# suntile.net
KiCad netlist of a schematic drawn in Altium Designer
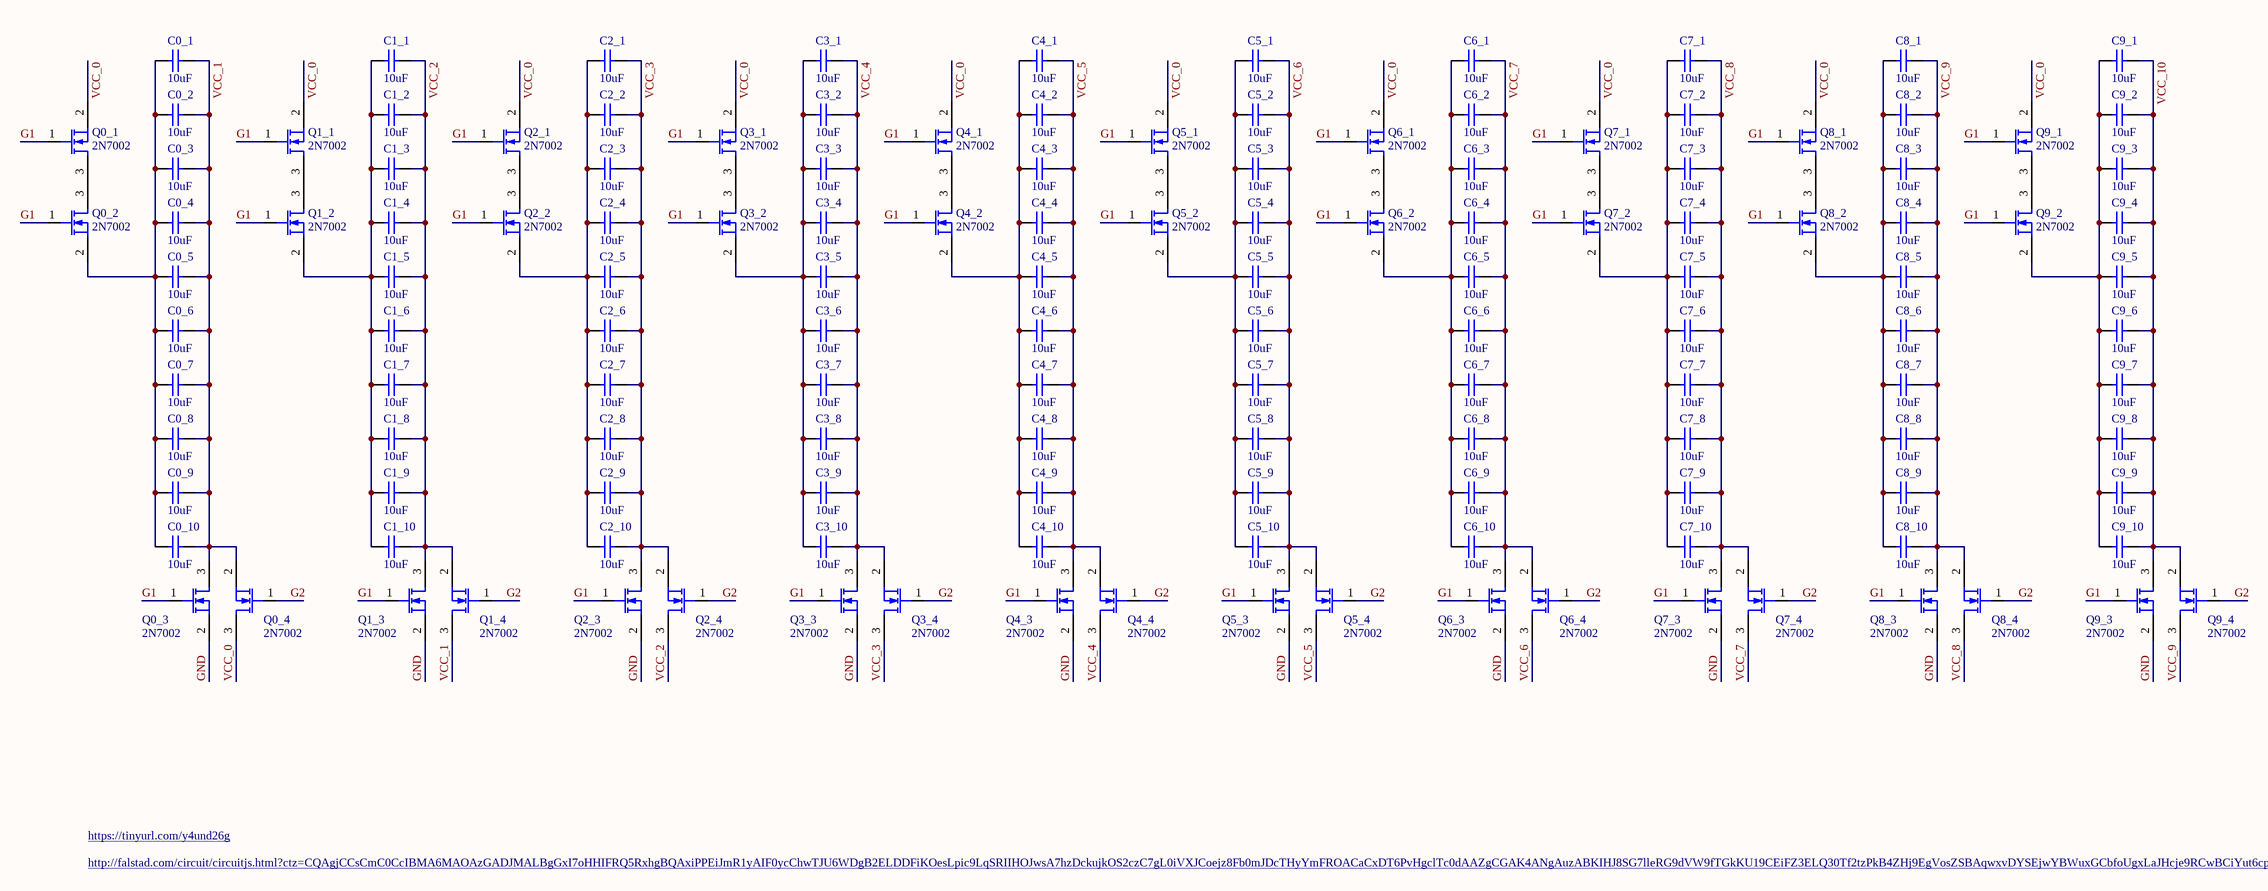
[diagram p0: suntile.SchDoc]

(export (version "E")
  (design (tool "Eeschema 10.0.6"))
  (components
    (comp (ref "C0_1")
      (value "10uF")
      (footprint "C_0402")
      (description "C - CAPACITOR - MLCC - 10uF - 6.3V - 0402")
      (fields (field (name "LCSC PART #") "C15525") (field (name "Comment") "CL05A106MQ5NUNC"))
      (libsource (lib "JLC_PCB") (part "CL05A106MQ5NUNC"))
    )
    (comp (ref "C0_2")
      (value "10uF")
      (footprint "C_0402")
      (description "C - CAPACITOR - MLCC - 10uF - 6.3V - 0402")
      (fields (field (name "LCSC PART #") "C15525") (field (name "Comment") "CL05A106MQ5NUNC"))
      (libsource (lib "JLC_PCB") (part "CL05A106MQ5NUNC"))
    )
    (comp (ref "C0_3")
      (value "10uF")
      (footprint "C_0402")
      (description "C - CAPACITOR - MLCC - 10uF - 6.3V - 0402")
      (fields (field (name "LCSC PART #") "C15525") (field (name "Comment") "CL05A106MQ5NUNC"))
      (libsource (lib "JLC_PCB") (part "CL05A106MQ5NUNC"))
    )
    (comp (ref "C0_4")
      (value "10uF")
      (footprint "C_0402")
      (description "C - CAPACITOR - MLCC - 10uF - 6.3V - 0402")
      (fields (field (name "LCSC PART #") "C15525") (field (name "Comment") "CL05A106MQ5NUNC"))
      (libsource (lib "JLC_PCB") (part "CL05A106MQ5NUNC"))
    )
    (comp (ref "C0_5")
      (value "10uF")
      (footprint "C_0402")
      (description "C - CAPACITOR - MLCC - 10uF - 6.3V - 0402")
      (fields (field (name "LCSC PART #") "C15525") (field (name "Comment") "CL05A106MQ5NUNC"))
      (libsource (lib "JLC_PCB") (part "CL05A106MQ5NUNC"))
    )
    (comp (ref "C0_6")
      (value "10uF")
      (footprint "C_0402")
      (description "C - CAPACITOR - MLCC - 10uF - 6.3V - 0402")
      (fields (field (name "LCSC PART #") "C15525") (field (name "Comment") "CL05A106MQ5NUNC"))
      (libsource (lib "JLC_PCB") (part "CL05A106MQ5NUNC"))
    )
    (comp (ref "C0_7")
      (value "10uF")
      (footprint "C_0402")
      (description "C - CAPACITOR - MLCC - 10uF - 6.3V - 0402")
      (fields (field (name "LCSC PART #") "C15525") (field (name "Comment") "CL05A106MQ5NUNC"))
      (libsource (lib "JLC_PCB") (part "CL05A106MQ5NUNC"))
    )
    (comp (ref "C0_8")
      (value "10uF")
      (footprint "C_0402")
      (description "C - CAPACITOR - MLCC - 10uF - 6.3V - 0402")
      (fields (field (name "LCSC PART #") "C15525") (field (name "Comment") "CL05A106MQ5NUNC"))
      (libsource (lib "JLC_PCB") (part "CL05A106MQ5NUNC"))
    )
    (comp (ref "C0_9")
      (value "10uF")
      (footprint "C_0402")
      (description "C - CAPACITOR - MLCC - 10uF - 6.3V - 0402")
      (fields (field (name "LCSC PART #") "C15525") (field (name "Comment") "CL05A106MQ5NUNC"))
      (libsource (lib "JLC_PCB") (part "CL05A106MQ5NUNC"))
    )
    (comp (ref "C0_10")
      (value "10uF")
      (footprint "C_0402")
      (description "C - CAPACITOR - MLCC - 10uF - 6.3V - 0402")
      (fields (field (name "LCSC PART #") "C15525") (field (name "Comment") "CL05A106MQ5NUNC"))
      (libsource (lib "JLC_PCB") (part "CL05A106MQ5NUNC"))
    )
    (comp (ref "C1_1")
      (value "10uF")
      (footprint "C_0402")
      (description "C - CAPACITOR - MLCC - 10uF - 6.3V - 0402")
      (fields (field (name "LCSC PART #") "C15525") (field (name "Comment") "CL05A106MQ5NUNC"))
      (libsource (lib "JLC_PCB") (part "CL05A106MQ5NUNC"))
    )
    (comp (ref "C1_2")
      (value "10uF")
      (footprint "C_0402")
      (description "C - CAPACITOR - MLCC - 10uF - 6.3V - 0402")
      (fields (field (name "LCSC PART #") "C15525") (field (name "Comment") "CL05A106MQ5NUNC"))
      (libsource (lib "JLC_PCB") (part "CL05A106MQ5NUNC"))
    )
    (comp (ref "C1_3")
      (value "10uF")
      (footprint "C_0402")
      (description "C - CAPACITOR - MLCC - 10uF - 6.3V - 0402")
      (fields (field (name "LCSC PART #") "C15525") (field (name "Comment") "CL05A106MQ5NUNC"))
      (libsource (lib "JLC_PCB") (part "CL05A106MQ5NUNC"))
    )
    (comp (ref "C1_4")
      (value "10uF")
      (footprint "C_0402")
      (description "C - CAPACITOR - MLCC - 10uF - 6.3V - 0402")
      (fields (field (name "LCSC PART #") "C15525") (field (name "Comment") "CL05A106MQ5NUNC"))
      (libsource (lib "JLC_PCB") (part "CL05A106MQ5NUNC"))
    )
    (comp (ref "C1_5")
      (value "10uF")
      (footprint "C_0402")
      (description "C - CAPACITOR - MLCC - 10uF - 6.3V - 0402")
      (fields (field (name "LCSC PART #") "C15525") (field (name "Comment") "CL05A106MQ5NUNC"))
      (libsource (lib "JLC_PCB") (part "CL05A106MQ5NUNC"))
    )
    (comp (ref "C1_6")
      (value "10uF")
      (footprint "C_0402")
      (description "C - CAPACITOR - MLCC - 10uF - 6.3V - 0402")
      (fields (field (name "LCSC PART #") "C15525") (field (name "Comment") "CL05A106MQ5NUNC"))
      (libsource (lib "JLC_PCB") (part "CL05A106MQ5NUNC"))
    )
    (comp (ref "C1_7")
      (value "10uF")
      (footprint "C_0402")
      (description "C - CAPACITOR - MLCC - 10uF - 6.3V - 0402")
      (fields (field (name "LCSC PART #") "C15525") (field (name "Comment") "CL05A106MQ5NUNC"))
      (libsource (lib "JLC_PCB") (part "CL05A106MQ5NUNC"))
    )
    (comp (ref "C1_8")
      (value "10uF")
      (footprint "C_0402")
      (description "C - CAPACITOR - MLCC - 10uF - 6.3V - 0402")
      (fields (field (name "LCSC PART #") "C15525") (field (name "Comment") "CL05A106MQ5NUNC"))
      (libsource (lib "JLC_PCB") (part "CL05A106MQ5NUNC"))
    )
    (comp (ref "C1_9")
      (value "10uF")
      (footprint "C_0402")
      (description "C - CAPACITOR - MLCC - 10uF - 6.3V - 0402")
      (fields (field (name "LCSC PART #") "C15525") (field (name "Comment") "CL05A106MQ5NUNC"))
      (libsource (lib "JLC_PCB") (part "CL05A106MQ5NUNC"))
    )
    (comp (ref "C1_10")
      (value "10uF")
      (footprint "C_0402")
      (description "C - CAPACITOR - MLCC - 10uF - 6.3V - 0402")
      (fields (field (name "LCSC PART #") "C15525") (field (name "Comment") "CL05A106MQ5NUNC"))
      (libsource (lib "JLC_PCB") (part "CL05A106MQ5NUNC"))
    )
    (comp (ref "C2_1")
      (value "10uF")
      (footprint "C_0402")
      (description "C - CAPACITOR - MLCC - 10uF - 6.3V - 0402")
      (fields (field (name "LCSC PART #") "C15525") (field (name "Comment") "CL05A106MQ5NUNC"))
      (libsource (lib "JLC_PCB") (part "CL05A106MQ5NUNC"))
    )
    (comp (ref "C2_2")
      (value "10uF")
      (footprint "C_0402")
      (description "C - CAPACITOR - MLCC - 10uF - 6.3V - 0402")
      (fields (field (name "LCSC PART #") "C15525") (field (name "Comment") "CL05A106MQ5NUNC"))
      (libsource (lib "JLC_PCB") (part "CL05A106MQ5NUNC"))
    )
    (comp (ref "C2_3")
      (value "10uF")
      (footprint "C_0402")
      (description "C - CAPACITOR - MLCC - 10uF - 6.3V - 0402")
      (fields (field (name "LCSC PART #") "C15525") (field (name "Comment") "CL05A106MQ5NUNC"))
      (libsource (lib "JLC_PCB") (part "CL05A106MQ5NUNC"))
    )
    (comp (ref "C2_4")
      (value "10uF")
      (footprint "C_0402")
      (description "C - CAPACITOR - MLCC - 10uF - 6.3V - 0402")
      (fields (field (name "LCSC PART #") "C15525") (field (name "Comment") "CL05A106MQ5NUNC"))
      (libsource (lib "JLC_PCB") (part "CL05A106MQ5NUNC"))
    )
    (comp (ref "C2_5")
      (value "10uF")
      (footprint "C_0402")
      (description "C - CAPACITOR - MLCC - 10uF - 6.3V - 0402")
      (fields (field (name "LCSC PART #") "C15525") (field (name "Comment") "CL05A106MQ5NUNC"))
      (libsource (lib "JLC_PCB") (part "CL05A106MQ5NUNC"))
    )
    (comp (ref "C2_6")
      (value "10uF")
      (footprint "C_0402")
      (description "C - CAPACITOR - MLCC - 10uF - 6.3V - 0402")
      (fields (field (name "LCSC PART #") "C15525") (field (name "Comment") "CL05A106MQ5NUNC"))
      (libsource (lib "JLC_PCB") (part "CL05A106MQ5NUNC"))
    )
    (comp (ref "C2_7")
      (value "10uF")
      (footprint "C_0402")
      (description "C - CAPACITOR - MLCC - 10uF - 6.3V - 0402")
      (fields (field (name "LCSC PART #") "C15525") (field (name "Comment") "CL05A106MQ5NUNC"))
      (libsource (lib "JLC_PCB") (part "CL05A106MQ5NUNC"))
    )
    (comp (ref "C2_8")
      (value "10uF")
      (footprint "C_0402")
      (description "C - CAPACITOR - MLCC - 10uF - 6.3V - 0402")
      (fields (field (name "LCSC PART #") "C15525") (field (name "Comment") "CL05A106MQ5NUNC"))
      (libsource (lib "JLC_PCB") (part "CL05A106MQ5NUNC"))
    )
    (comp (ref "C2_9")
      (value "10uF")
      (footprint "C_0402")
      (description "C - CAPACITOR - MLCC - 10uF - 6.3V - 0402")
      (fields (field (name "LCSC PART #") "C15525") (field (name "Comment") "CL05A106MQ5NUNC"))
      (libsource (lib "JLC_PCB") (part "CL05A106MQ5NUNC"))
    )
    (comp (ref "C2_10")
      (value "10uF")
      (footprint "C_0402")
      (description "C - CAPACITOR - MLCC - 10uF - 6.3V - 0402")
      (fields (field (name "LCSC PART #") "C15525") (field (name "Comment") "CL05A106MQ5NUNC"))
      (libsource (lib "JLC_PCB") (part "CL05A106MQ5NUNC"))
    )
    (comp (ref "C3_1")
      (value "10uF")
      (footprint "C_0402")
      (description "C - CAPACITOR - MLCC - 10uF - 6.3V - 0402")
      (fields (field (name "LCSC PART #") "C15525") (field (name "Comment") "CL05A106MQ5NUNC"))
      (libsource (lib "JLC_PCB") (part "CL05A106MQ5NUNC"))
    )
    (comp (ref "C3_2")
      (value "10uF")
      (footprint "C_0402")
      (description "C - CAPACITOR - MLCC - 10uF - 6.3V - 0402")
      (fields (field (name "LCSC PART #") "C15525") (field (name "Comment") "CL05A106MQ5NUNC"))
      (libsource (lib "JLC_PCB") (part "CL05A106MQ5NUNC"))
    )
    (comp (ref "C3_3")
      (value "10uF")
      (footprint "C_0402")
      (description "C - CAPACITOR - MLCC - 10uF - 6.3V - 0402")
      (fields (field (name "LCSC PART #") "C15525") (field (name "Comment") "CL05A106MQ5NUNC"))
      (libsource (lib "JLC_PCB") (part "CL05A106MQ5NUNC"))
    )
    (comp (ref "C3_4")
      (value "10uF")
      (footprint "C_0402")
      (description "C - CAPACITOR - MLCC - 10uF - 6.3V - 0402")
      (fields (field (name "LCSC PART #") "C15525") (field (name "Comment") "CL05A106MQ5NUNC"))
      (libsource (lib "JLC_PCB") (part "CL05A106MQ5NUNC"))
    )
    (comp (ref "C3_5")
      (value "10uF")
      (footprint "C_0402")
      (description "C - CAPACITOR - MLCC - 10uF - 6.3V - 0402")
      (fields (field (name "LCSC PART #") "C15525") (field (name "Comment") "CL05A106MQ5NUNC"))
      (libsource (lib "JLC_PCB") (part "CL05A106MQ5NUNC"))
    )
    (comp (ref "C3_6")
      (value "10uF")
      (footprint "C_0402")
      (description "C - CAPACITOR - MLCC - 10uF - 6.3V - 0402")
      (fields (field (name "LCSC PART #") "C15525") (field (name "Comment") "CL05A106MQ5NUNC"))
      (libsource (lib "JLC_PCB") (part "CL05A106MQ5NUNC"))
    )
    (comp (ref "C3_7")
      (value "10uF")
      (footprint "C_0402")
      (description "C - CAPACITOR - MLCC - 10uF - 6.3V - 0402")
      (fields (field (name "LCSC PART #") "C15525") (field (name "Comment") "CL05A106MQ5NUNC"))
      (libsource (lib "JLC_PCB") (part "CL05A106MQ5NUNC"))
    )
    (comp (ref "C3_8")
      (value "10uF")
      (footprint "C_0402")
      (description "C - CAPACITOR - MLCC - 10uF - 6.3V - 0402")
      (fields (field (name "LCSC PART #") "C15525") (field (name "Comment") "CL05A106MQ5NUNC"))
      (libsource (lib "JLC_PCB") (part "CL05A106MQ5NUNC"))
    )
    (comp (ref "C3_9")
      (value "10uF")
      (footprint "C_0402")
      (description "C - CAPACITOR - MLCC - 10uF - 6.3V - 0402")
      (fields (field (name "LCSC PART #") "C15525") (field (name "Comment") "CL05A106MQ5NUNC"))
      (libsource (lib "JLC_PCB") (part "CL05A106MQ5NUNC"))
    )
    (comp (ref "C3_10")
      (value "10uF")
      (footprint "C_0402")
      (description "C - CAPACITOR - MLCC - 10uF - 6.3V - 0402")
      (fields (field (name "LCSC PART #") "C15525") (field (name "Comment") "CL05A106MQ5NUNC"))
      (libsource (lib "JLC_PCB") (part "CL05A106MQ5NUNC"))
    )
    (comp (ref "C4_1")
      (value "10uF")
      (footprint "C_0402")
      (description "C - CAPACITOR - MLCC - 10uF - 6.3V - 0402")
      (fields (field (name "LCSC PART #") "C15525") (field (name "Comment") "CL05A106MQ5NUNC"))
      (libsource (lib "JLC_PCB") (part "CL05A106MQ5NUNC"))
    )
    (comp (ref "C4_2")
      (value "10uF")
      (footprint "C_0402")
      (description "C - CAPACITOR - MLCC - 10uF - 6.3V - 0402")
      (fields (field (name "LCSC PART #") "C15525") (field (name "Comment") "CL05A106MQ5NUNC"))
      (libsource (lib "JLC_PCB") (part "CL05A106MQ5NUNC"))
    )
    (comp (ref "C4_3")
      (value "10uF")
      (footprint "C_0402")
      (description "C - CAPACITOR - MLCC - 10uF - 6.3V - 0402")
      (fields (field (name "LCSC PART #") "C15525") (field (name "Comment") "CL05A106MQ5NUNC"))
      (libsource (lib "JLC_PCB") (part "CL05A106MQ5NUNC"))
    )
    (comp (ref "C4_4")
      (value "10uF")
      (footprint "C_0402")
      (description "C - CAPACITOR - MLCC - 10uF - 6.3V - 0402")
      (fields (field (name "LCSC PART #") "C15525") (field (name "Comment") "CL05A106MQ5NUNC"))
      (libsource (lib "JLC_PCB") (part "CL05A106MQ5NUNC"))
    )
    (comp (ref "C4_5")
      (value "10uF")
      (footprint "C_0402")
      (description "C - CAPACITOR - MLCC - 10uF - 6.3V - 0402")
      (fields (field (name "LCSC PART #") "C15525") (field (name "Comment") "CL05A106MQ5NUNC"))
      (libsource (lib "JLC_PCB") (part "CL05A106MQ5NUNC"))
    )
    (comp (ref "C4_6")
      (value "10uF")
      (footprint "C_0402")
      (description "C - CAPACITOR - MLCC - 10uF - 6.3V - 0402")
      (fields (field (name "LCSC PART #") "C15525") (field (name "Comment") "CL05A106MQ5NUNC"))
      (libsource (lib "JLC_PCB") (part "CL05A106MQ5NUNC"))
    )
    (comp (ref "C4_7")
      (value "10uF")
      (footprint "C_0402")
      (description "C - CAPACITOR - MLCC - 10uF - 6.3V - 0402")
      (fields (field (name "LCSC PART #") "C15525") (field (name "Comment") "CL05A106MQ5NUNC"))
      (libsource (lib "JLC_PCB") (part "CL05A106MQ5NUNC"))
    )
    (comp (ref "C4_8")
      (value "10uF")
      (footprint "C_0402")
      (description "C - CAPACITOR - MLCC - 10uF - 6.3V - 0402")
      (fields (field (name "LCSC PART #") "C15525") (field (name "Comment") "CL05A106MQ5NUNC"))
      (libsource (lib "JLC_PCB") (part "CL05A106MQ5NUNC"))
    )
    (comp (ref "C4_9")
      (value "10uF")
      (footprint "C_0402")
      (description "C - CAPACITOR - MLCC - 10uF - 6.3V - 0402")
      (fields (field (name "LCSC PART #") "C15525") (field (name "Comment") "CL05A106MQ5NUNC"))
      (libsource (lib "JLC_PCB") (part "CL05A106MQ5NUNC"))
    )
    (comp (ref "C4_10")
      (value "10uF")
      (footprint "C_0402")
      (description "C - CAPACITOR - MLCC - 10uF - 6.3V - 0402")
      (fields (field (name "LCSC PART #") "C15525") (field (name "Comment") "CL05A106MQ5NUNC"))
      (libsource (lib "JLC_PCB") (part "CL05A106MQ5NUNC"))
    )
    (comp (ref "C5_1")
      (value "10uF")
      (footprint "C_0402")
      (description "C - CAPACITOR - MLCC - 10uF - 6.3V - 0402")
      (fields (field (name "LCSC PART #") "C15525") (field (name "Comment") "CL05A106MQ5NUNC"))
      (libsource (lib "JLC_PCB") (part "CL05A106MQ5NUNC"))
    )
    (comp (ref "C5_2")
      (value "10uF")
      (footprint "C_0402")
      (description "C - CAPACITOR - MLCC - 10uF - 6.3V - 0402")
      (fields (field (name "LCSC PART #") "C15525") (field (name "Comment") "CL05A106MQ5NUNC"))
      (libsource (lib "JLC_PCB") (part "CL05A106MQ5NUNC"))
    )
    (comp (ref "C5_3")
      (value "10uF")
      (footprint "C_0402")
      (description "C - CAPACITOR - MLCC - 10uF - 6.3V - 0402")
      (fields (field (name "LCSC PART #") "C15525") (field (name "Comment") "CL05A106MQ5NUNC"))
      (libsource (lib "JLC_PCB") (part "CL05A106MQ5NUNC"))
    )
    (comp (ref "C5_4")
      (value "10uF")
      (footprint "C_0402")
      (description "C - CAPACITOR - MLCC - 10uF - 6.3V - 0402")
      (fields (field (name "LCSC PART #") "C15525") (field (name "Comment") "CL05A106MQ5NUNC"))
      (libsource (lib "JLC_PCB") (part "CL05A106MQ5NUNC"))
    )
    (comp (ref "C5_5")
      (value "10uF")
      (footprint "C_0402")
      (description "C - CAPACITOR - MLCC - 10uF - 6.3V - 0402")
      (fields (field (name "LCSC PART #") "C15525") (field (name "Comment") "CL05A106MQ5NUNC"))
      (libsource (lib "JLC_PCB") (part "CL05A106MQ5NUNC"))
    )
    (comp (ref "C5_6")
      (value "10uF")
      (footprint "C_0402")
      (description "C - CAPACITOR - MLCC - 10uF - 6.3V - 0402")
      (fields (field (name "LCSC PART #") "C15525") (field (name "Comment") "CL05A106MQ5NUNC"))
      (libsource (lib "JLC_PCB") (part "CL05A106MQ5NUNC"))
    )
    (comp (ref "C5_7")
      (value "10uF")
      (footprint "C_0402")
      (description "C - CAPACITOR - MLCC - 10uF - 6.3V - 0402")
      (fields (field (name "LCSC PART #") "C15525") (field (name "Comment") "CL05A106MQ5NUNC"))
      (libsource (lib "JLC_PCB") (part "CL05A106MQ5NUNC"))
    )
    (comp (ref "C5_8")
      (value "10uF")
      (footprint "C_0402")
      (description "C - CAPACITOR - MLCC - 10uF - 6.3V - 0402")
      (fields (field (name "LCSC PART #") "C15525") (field (name "Comment") "CL05A106MQ5NUNC"))
      (libsource (lib "JLC_PCB") (part "CL05A106MQ5NUNC"))
    )
    (comp (ref "C5_9")
      (value "10uF")
      (footprint "C_0402")
      (description "C - CAPACITOR - MLCC - 10uF - 6.3V - 0402")
      (fields (field (name "LCSC PART #") "C15525") (field (name "Comment") "CL05A106MQ5NUNC"))
      (libsource (lib "JLC_PCB") (part "CL05A106MQ5NUNC"))
    )
    (comp (ref "C5_10")
      (value "10uF")
      (footprint "C_0402")
      (description "C - CAPACITOR - MLCC - 10uF - 6.3V - 0402")
      (fields (field (name "LCSC PART #") "C15525") (field (name "Comment") "CL05A106MQ5NUNC"))
      (libsource (lib "JLC_PCB") (part "CL05A106MQ5NUNC"))
    )
    (comp (ref "C6_1")
      (value "10uF")
      (footprint "C_0402")
      (description "C - CAPACITOR - MLCC - 10uF - 6.3V - 0402")
      (fields (field (name "LCSC PART #") "C15525") (field (name "Comment") "CL05A106MQ5NUNC"))
      (libsource (lib "JLC_PCB") (part "CL05A106MQ5NUNC"))
    )
    (comp (ref "C6_2")
      (value "10uF")
      (footprint "C_0402")
      (description "C - CAPACITOR - MLCC - 10uF - 6.3V - 0402")
      (fields (field (name "LCSC PART #") "C15525") (field (name "Comment") "CL05A106MQ5NUNC"))
      (libsource (lib "JLC_PCB") (part "CL05A106MQ5NUNC"))
    )
    (comp (ref "C6_3")
      (value "10uF")
      (footprint "C_0402")
      (description "C - CAPACITOR - MLCC - 10uF - 6.3V - 0402")
      (fields (field (name "LCSC PART #") "C15525") (field (name "Comment") "CL05A106MQ5NUNC"))
      (libsource (lib "JLC_PCB") (part "CL05A106MQ5NUNC"))
    )
    (comp (ref "C6_4")
      (value "10uF")
      (footprint "C_0402")
      (description "C - CAPACITOR - MLCC - 10uF - 6.3V - 0402")
      (fields (field (name "LCSC PART #") "C15525") (field (name "Comment") "CL05A106MQ5NUNC"))
      (libsource (lib "JLC_PCB") (part "CL05A106MQ5NUNC"))
    )
    (comp (ref "C6_5")
      (value "10uF")
      (footprint "C_0402")
      (description "C - CAPACITOR - MLCC - 10uF - 6.3V - 0402")
      (fields (field (name "LCSC PART #") "C15525") (field (name "Comment") "CL05A106MQ5NUNC"))
      (libsource (lib "JLC_PCB") (part "CL05A106MQ5NUNC"))
    )
    (comp (ref "C6_6")
      (value "10uF")
      (footprint "C_0402")
      (description "C - CAPACITOR - MLCC - 10uF - 6.3V - 0402")
      (fields (field (name "LCSC PART #") "C15525") (field (name "Comment") "CL05A106MQ5NUNC"))
      (libsource (lib "JLC_PCB") (part "CL05A106MQ5NUNC"))
    )
    (comp (ref "C6_7")
      (value "10uF")
      (footprint "C_0402")
      (description "C - CAPACITOR - MLCC - 10uF - 6.3V - 0402")
      (fields (field (name "LCSC PART #") "C15525") (field (name "Comment") "CL05A106MQ5NUNC"))
      (libsource (lib "JLC_PCB") (part "CL05A106MQ5NUNC"))
    )
    (comp (ref "C6_8")
      (value "10uF")
      (footprint "C_0402")
      (description "C - CAPACITOR - MLCC - 10uF - 6.3V - 0402")
      (fields (field (name "LCSC PART #") "C15525") (field (name "Comment") "CL05A106MQ5NUNC"))
      (libsource (lib "JLC_PCB") (part "CL05A106MQ5NUNC"))
    )
    (comp (ref "C6_9")
      (value "10uF")
      (footprint "C_0402")
      (description "C - CAPACITOR - MLCC - 10uF - 6.3V - 0402")
      (fields (field (name "LCSC PART #") "C15525") (field (name "Comment") "CL05A106MQ5NUNC"))
      (libsource (lib "JLC_PCB") (part "CL05A106MQ5NUNC"))
    )
    (comp (ref "C6_10")
      (value "10uF")
      (footprint "C_0402")
      (description "C - CAPACITOR - MLCC - 10uF - 6.3V - 0402")
      (fields (field (name "LCSC PART #") "C15525") (field (name "Comment") "CL05A106MQ5NUNC"))
      (libsource (lib "JLC_PCB") (part "CL05A106MQ5NUNC"))
    )
    (comp (ref "C7_1")
      (value "10uF")
      (footprint "C_0402")
      (description "C - CAPACITOR - MLCC - 10uF - 6.3V - 0402")
      (fields (field (name "LCSC PART #") "C15525") (field (name "Comment") "CL05A106MQ5NUNC"))
      (libsource (lib "JLC_PCB") (part "CL05A106MQ5NUNC"))
    )
    (comp (ref "C7_2")
      (value "10uF")
      (footprint "C_0402")
      (description "C - CAPACITOR - MLCC - 10uF - 6.3V - 0402")
      (fields (field (name "LCSC PART #") "C15525") (field (name "Comment") "CL05A106MQ5NUNC"))
      (libsource (lib "JLC_PCB") (part "CL05A106MQ5NUNC"))
    )
    (comp (ref "C7_3")
      (value "10uF")
      (footprint "C_0402")
      (description "C - CAPACITOR - MLCC - 10uF - 6.3V - 0402")
      (fields (field (name "LCSC PART #") "C15525") (field (name "Comment") "CL05A106MQ5NUNC"))
      (libsource (lib "JLC_PCB") (part "CL05A106MQ5NUNC"))
    )
    (comp (ref "C7_4")
      (value "10uF")
      (footprint "C_0402")
      (description "C - CAPACITOR - MLCC - 10uF - 6.3V - 0402")
      (fields (field (name "LCSC PART #") "C15525") (field (name "Comment") "CL05A106MQ5NUNC"))
      (libsource (lib "JLC_PCB") (part "CL05A106MQ5NUNC"))
    )
    (comp (ref "C7_5")
      (value "10uF")
      (footprint "C_0402")
      (description "C - CAPACITOR - MLCC - 10uF - 6.3V - 0402")
      (fields (field (name "LCSC PART #") "C15525") (field (name "Comment") "CL05A106MQ5NUNC"))
      (libsource (lib "JLC_PCB") (part "CL05A106MQ5NUNC"))
    )
    (comp (ref "C7_6")
      (value "10uF")
      (footprint "C_0402")
      (description "C - CAPACITOR - MLCC - 10uF - 6.3V - 0402")
      (fields (field (name "LCSC PART #") "C15525") (field (name "Comment") "CL05A106MQ5NUNC"))
      (libsource (lib "JLC_PCB") (part "CL05A106MQ5NUNC"))
    )
    (comp (ref "C7_7")
      (value "10uF")
      (footprint "C_0402")
      (description "C - CAPACITOR - MLCC - 10uF - 6.3V - 0402")
      (fields (field (name "LCSC PART #") "C15525") (field (name "Comment") "CL05A106MQ5NUNC"))
      (libsource (lib "JLC_PCB") (part "CL05A106MQ5NUNC"))
    )
    (comp (ref "C7_8")
      (value "10uF")
      (footprint "C_0402")
      (description "C - CAPACITOR - MLCC - 10uF - 6.3V - 0402")
      (fields (field (name "LCSC PART #") "C15525") (field (name "Comment") "CL05A106MQ5NUNC"))
      (libsource (lib "JLC_PCB") (part "CL05A106MQ5NUNC"))
    )
    (comp (ref "C7_9")
      (value "10uF")
      (footprint "C_0402")
      (description "C - CAPACITOR - MLCC - 10uF - 6.3V - 0402")
      (fields (field (name "LCSC PART #") "C15525") (field (name "Comment") "CL05A106MQ5NUNC"))
      (libsource (lib "JLC_PCB") (part "CL05A106MQ5NUNC"))
    )
    (comp (ref "C7_10")
      (value "10uF")
      (footprint "C_0402")
      (description "C - CAPACITOR - MLCC - 10uF - 6.3V - 0402")
      (fields (field (name "LCSC PART #") "C15525") (field (name "Comment") "CL05A106MQ5NUNC"))
      (libsource (lib "JLC_PCB") (part "CL05A106MQ5NUNC"))
    )
    (comp (ref "C8_1")
      (value "10uF")
      (footprint "C_0402")
      (description "C - CAPACITOR - MLCC - 10uF - 6.3V - 0402")
      (fields (field (name "LCSC PART #") "C15525") (field (name "Comment") "CL05A106MQ5NUNC"))
      (libsource (lib "JLC_PCB") (part "CL05A106MQ5NUNC"))
    )
    (comp (ref "C8_2")
      (value "10uF")
      (footprint "C_0402")
      (description "C - CAPACITOR - MLCC - 10uF - 6.3V - 0402")
      (fields (field (name "LCSC PART #") "C15525") (field (name "Comment") "CL05A106MQ5NUNC"))
      (libsource (lib "JLC_PCB") (part "CL05A106MQ5NUNC"))
    )
    (comp (ref "C8_3")
      (value "10uF")
      (footprint "C_0402")
      (description "C - CAPACITOR - MLCC - 10uF - 6.3V - 0402")
      (fields (field (name "LCSC PART #") "C15525") (field (name "Comment") "CL05A106MQ5NUNC"))
      (libsource (lib "JLC_PCB") (part "CL05A106MQ5NUNC"))
    )
    (comp (ref "C8_4")
      (value "10uF")
      (footprint "C_0402")
      (description "C - CAPACITOR - MLCC - 10uF - 6.3V - 0402")
      (fields (field (name "LCSC PART #") "C15525") (field (name "Comment") "CL05A106MQ5NUNC"))
      (libsource (lib "JLC_PCB") (part "CL05A106MQ5NUNC"))
    )
    (comp (ref "C8_5")
      (value "10uF")
      (footprint "C_0402")
      (description "C - CAPACITOR - MLCC - 10uF - 6.3V - 0402")
      (fields (field (name "LCSC PART #") "C15525") (field (name "Comment") "CL05A106MQ5NUNC"))
      (libsource (lib "JLC_PCB") (part "CL05A106MQ5NUNC"))
    )
    (comp (ref "C8_6")
      (value "10uF")
      (footprint "C_0402")
      (description "C - CAPACITOR - MLCC - 10uF - 6.3V - 0402")
      (fields (field (name "LCSC PART #") "C15525") (field (name "Comment") "CL05A106MQ5NUNC"))
      (libsource (lib "JLC_PCB") (part "CL05A106MQ5NUNC"))
    )
    (comp (ref "C8_7")
      (value "10uF")
      (footprint "C_0402")
      (description "C - CAPACITOR - MLCC - 10uF - 6.3V - 0402")
      (fields (field (name "LCSC PART #") "C15525") (field (name "Comment") "CL05A106MQ5NUNC"))
      (libsource (lib "JLC_PCB") (part "CL05A106MQ5NUNC"))
    )
    (comp (ref "C8_8")
      (value "10uF")
      (footprint "C_0402")
      (description "C - CAPACITOR - MLCC - 10uF - 6.3V - 0402")
      (fields (field (name "LCSC PART #") "C15525") (field (name "Comment") "CL05A106MQ5NUNC"))
      (libsource (lib "JLC_PCB") (part "CL05A106MQ5NUNC"))
    )
    (comp (ref "C8_9")
      (value "10uF")
      (footprint "C_0402")
      (description "C - CAPACITOR - MLCC - 10uF - 6.3V - 0402")
      (fields (field (name "LCSC PART #") "C15525") (field (name "Comment") "CL05A106MQ5NUNC"))
      (libsource (lib "JLC_PCB") (part "CL05A106MQ5NUNC"))
    )
    (comp (ref "C8_10")
      (value "10uF")
      (footprint "C_0402")
      (description "C - CAPACITOR - MLCC - 10uF - 6.3V - 0402")
      (fields (field (name "LCSC PART #") "C15525") (field (name "Comment") "CL05A106MQ5NUNC"))
      (libsource (lib "JLC_PCB") (part "CL05A106MQ5NUNC"))
    )
    (comp (ref "C9_1")
      (value "10uF")
      (footprint "C_0402")
      (description "C - CAPACITOR - MLCC - 10uF - 6.3V - 0402")
      (fields (field (name "LCSC PART #") "C15525") (field (name "Comment") "CL05A106MQ5NUNC"))
      (libsource (lib "JLC_PCB") (part "CL05A106MQ5NUNC"))
    )
    (comp (ref "C9_2")
      (value "10uF")
      (footprint "C_0402")
      (description "C - CAPACITOR - MLCC - 10uF - 6.3V - 0402")
      (fields (field (name "LCSC PART #") "C15525") (field (name "Comment") "CL05A106MQ5NUNC"))
      (libsource (lib "JLC_PCB") (part "CL05A106MQ5NUNC"))
    )
    (comp (ref "C9_3")
      (value "10uF")
      (footprint "C_0402")
      (description "C - CAPACITOR - MLCC - 10uF - 6.3V - 0402")
      (fields (field (name "LCSC PART #") "C15525") (field (name "Comment") "CL05A106MQ5NUNC"))
      (libsource (lib "JLC_PCB") (part "CL05A106MQ5NUNC"))
    )
    (comp (ref "C9_4")
      (value "10uF")
      (footprint "C_0402")
      (description "C - CAPACITOR - MLCC - 10uF - 6.3V - 0402")
      (fields (field (name "LCSC PART #") "C15525") (field (name "Comment") "CL05A106MQ5NUNC"))
      (libsource (lib "JLC_PCB") (part "CL05A106MQ5NUNC"))
    )
    (comp (ref "C9_5")
      (value "10uF")
      (footprint "C_0402")
      (description "C - CAPACITOR - MLCC - 10uF - 6.3V - 0402")
      (fields (field (name "LCSC PART #") "C15525") (field (name "Comment") "CL05A106MQ5NUNC"))
      (libsource (lib "JLC_PCB") (part "CL05A106MQ5NUNC"))
    )
    (comp (ref "C9_6")
      (value "10uF")
      (footprint "C_0402")
      (description "C - CAPACITOR - MLCC - 10uF - 6.3V - 0402")
      (fields (field (name "LCSC PART #") "C15525") (field (name "Comment") "CL05A106MQ5NUNC"))
      (libsource (lib "JLC_PCB") (part "CL05A106MQ5NUNC"))
    )
    (comp (ref "C9_7")
      (value "10uF")
      (footprint "C_0402")
      (description "C - CAPACITOR - MLCC - 10uF - 6.3V - 0402")
      (fields (field (name "LCSC PART #") "C15525") (field (name "Comment") "CL05A106MQ5NUNC"))
      (libsource (lib "JLC_PCB") (part "CL05A106MQ5NUNC"))
    )
    (comp (ref "C9_8")
      (value "10uF")
      (footprint "C_0402")
      (description "C - CAPACITOR - MLCC - 10uF - 6.3V - 0402")
      (fields (field (name "LCSC PART #") "C15525") (field (name "Comment") "CL05A106MQ5NUNC"))
      (libsource (lib "JLC_PCB") (part "CL05A106MQ5NUNC"))
    )
    (comp (ref "C9_9")
      (value "10uF")
      (footprint "C_0402")
      (description "C - CAPACITOR - MLCC - 10uF - 6.3V - 0402")
      (fields (field (name "LCSC PART #") "C15525") (field (name "Comment") "CL05A106MQ5NUNC"))
      (libsource (lib "JLC_PCB") (part "CL05A106MQ5NUNC"))
    )
    (comp (ref "C9_10")
      (value "10uF")
      (footprint "C_0402")
      (description "C - CAPACITOR - MLCC - 10uF - 6.3V - 0402")
      (fields (field (name "LCSC PART #") "C15525") (field (name "Comment") "CL05A106MQ5NUNC"))
      (libsource (lib "JLC_PCB") (part "CL05A106MQ5NUNC"))
    )
    (comp (ref "Q0_1")
      (value "2N7002")
      (footprint "TO-236AB")
      (description "Q - TRANSISTOR - MOSFET (N) - 60V - 200mW")
      (fields (field (name "LCSC PART #") "C8545"))
      (libsource (lib "JLC_PCB") (part "2N7002"))
    )
    (comp (ref "Q0_2")
      (value "2N7002")
      (footprint "TO-236AB")
      (description "Q - TRANSISTOR - MOSFET (N) - 60V - 200mW")
      (fields (field (name "LCSC PART #") "C8545"))
      (libsource (lib "JLC_PCB") (part "2N7002"))
    )
    (comp (ref "Q0_3")
      (value "2N7002")
      (footprint "TO-236AB")
      (description "Q - TRANSISTOR - MOSFET (N) - 60V - 200mW")
      (fields (field (name "LCSC PART #") "C8545"))
      (libsource (lib "JLC_PCB") (part "2N7002"))
    )
    (comp (ref "Q0_4")
      (value "2N7002")
      (footprint "TO-236AB")
      (description "Q - TRANSISTOR - MOSFET (N) - 60V - 200mW")
      (fields (field (name "LCSC PART #") "C8545"))
      (libsource (lib "JLC_PCB") (part "2N7002"))
    )
    (comp (ref "Q1_1")
      (value "2N7002")
      (footprint "TO-236AB")
      (description "Q - TRANSISTOR - MOSFET (N) - 60V - 200mW")
      (fields (field (name "LCSC PART #") "C8545"))
      (libsource (lib "JLC_PCB") (part "2N7002"))
    )
    (comp (ref "Q1_2")
      (value "2N7002")
      (footprint "TO-236AB")
      (description "Q - TRANSISTOR - MOSFET (N) - 60V - 200mW")
      (fields (field (name "LCSC PART #") "C8545"))
      (libsource (lib "JLC_PCB") (part "2N7002"))
    )
    (comp (ref "Q1_3")
      (value "2N7002")
      (footprint "TO-236AB")
      (description "Q - TRANSISTOR - MOSFET (N) - 60V - 200mW")
      (fields (field (name "LCSC PART #") "C8545"))
      (libsource (lib "JLC_PCB") (part "2N7002"))
    )
    (comp (ref "Q1_4")
      (value "2N7002")
      (footprint "TO-236AB")
      (description "Q - TRANSISTOR - MOSFET (N) - 60V - 200mW")
      (fields (field (name "LCSC PART #") "C8545"))
      (libsource (lib "JLC_PCB") (part "2N7002"))
    )
    (comp (ref "Q2_1")
      (value "2N7002")
      (footprint "TO-236AB")
      (description "Q - TRANSISTOR - MOSFET (N) - 60V - 200mW")
      (fields (field (name "LCSC PART #") "C8545"))
      (libsource (lib "JLC_PCB") (part "2N7002"))
    )
    (comp (ref "Q2_2")
      (value "2N7002")
      (footprint "TO-236AB")
      (description "Q - TRANSISTOR - MOSFET (N) - 60V - 200mW")
      (fields (field (name "LCSC PART #") "C8545"))
      (libsource (lib "JLC_PCB") (part "2N7002"))
    )
    (comp (ref "Q2_3")
      (value "2N7002")
      (footprint "TO-236AB")
      (description "Q - TRANSISTOR - MOSFET (N) - 60V - 200mW")
      (fields (field (name "LCSC PART #") "C8545"))
      (libsource (lib "JLC_PCB") (part "2N7002"))
    )
    (comp (ref "Q2_4")
      (value "2N7002")
      (footprint "TO-236AB")
      (description "Q - TRANSISTOR - MOSFET (N) - 60V - 200mW")
      (fields (field (name "LCSC PART #") "C8545"))
      (libsource (lib "JLC_PCB") (part "2N7002"))
    )
    (comp (ref "Q3_1")
      (value "2N7002")
      (footprint "TO-236AB")
      (description "Q - TRANSISTOR - MOSFET (N) - 60V - 200mW")
      (fields (field (name "LCSC PART #") "C8545"))
      (libsource (lib "JLC_PCB") (part "2N7002"))
    )
    (comp (ref "Q3_2")
      (value "2N7002")
      (footprint "TO-236AB")
      (description "Q - TRANSISTOR - MOSFET (N) - 60V - 200mW")
      (fields (field (name "LCSC PART #") "C8545"))
      (libsource (lib "JLC_PCB") (part "2N7002"))
    )
    (comp (ref "Q3_3")
      (value "2N7002")
      (footprint "TO-236AB")
      (description "Q - TRANSISTOR - MOSFET (N) - 60V - 200mW")
      (fields (field (name "LCSC PART #") "C8545"))
      (libsource (lib "JLC_PCB") (part "2N7002"))
    )
    (comp (ref "Q3_4")
      (value "2N7002")
      (footprint "TO-236AB")
      (description "Q - TRANSISTOR - MOSFET (N) - 60V - 200mW")
      (fields (field (name "LCSC PART #") "C8545"))
      (libsource (lib "JLC_PCB") (part "2N7002"))
    )
    (comp (ref "Q4_1")
      (value "2N7002")
      (footprint "TO-236AB")
      (description "Q - TRANSISTOR - MOSFET (N) - 60V - 200mW")
      (fields (field (name "LCSC PART #") "C8545"))
      (libsource (lib "JLC_PCB") (part "2N7002"))
    )
    (comp (ref "Q4_2")
      (value "2N7002")
      (footprint "TO-236AB")
      (description "Q - TRANSISTOR - MOSFET (N) - 60V - 200mW")
      (fields (field (name "LCSC PART #") "C8545"))
      (libsource (lib "JLC_PCB") (part "2N7002"))
    )
    (comp (ref "Q4_3")
      (value "2N7002")
      (footprint "TO-236AB")
      (description "Q - TRANSISTOR - MOSFET (N) - 60V - 200mW")
      (fields (field (name "LCSC PART #") "C8545"))
      (libsource (lib "JLC_PCB") (part "2N7002"))
    )
    (comp (ref "Q4_4")
      (value "2N7002")
      (footprint "TO-236AB")
      (description "Q - TRANSISTOR - MOSFET (N) - 60V - 200mW")
      (fields (field (name "LCSC PART #") "C8545"))
      (libsource (lib "JLC_PCB") (part "2N7002"))
    )
    (comp (ref "Q5_1")
      (value "2N7002")
      (footprint "TO-236AB")
      (description "Q - TRANSISTOR - MOSFET (N) - 60V - 200mW")
      (fields (field (name "LCSC PART #") "C8545"))
      (libsource (lib "JLC_PCB") (part "2N7002"))
    )
    (comp (ref "Q5_2")
      (value "2N7002")
      (footprint "TO-236AB")
      (description "Q - TRANSISTOR - MOSFET (N) - 60V - 200mW")
      (fields (field (name "LCSC PART #") "C8545"))
      (libsource (lib "JLC_PCB") (part "2N7002"))
    )
    (comp (ref "Q5_3")
      (value "2N7002")
      (footprint "TO-236AB")
      (description "Q - TRANSISTOR - MOSFET (N) - 60V - 200mW")
      (fields (field (name "LCSC PART #") "C8545"))
      (libsource (lib "JLC_PCB") (part "2N7002"))
    )
    (comp (ref "Q5_4")
      (value "2N7002")
      (footprint "TO-236AB")
      (description "Q - TRANSISTOR - MOSFET (N) - 60V - 200mW")
      (fields (field (name "LCSC PART #") "C8545"))
      (libsource (lib "JLC_PCB") (part "2N7002"))
    )
    (comp (ref "Q6_1")
      (value "2N7002")
      (footprint "TO-236AB")
      (description "Q - TRANSISTOR - MOSFET (N) - 60V - 200mW")
      (fields (field (name "LCSC PART #") "C8545"))
      (libsource (lib "JLC_PCB") (part "2N7002"))
    )
    (comp (ref "Q6_2")
      (value "2N7002")
      (footprint "TO-236AB")
      (description "Q - TRANSISTOR - MOSFET (N) - 60V - 200mW")
      (fields (field (name "LCSC PART #") "C8545"))
      (libsource (lib "JLC_PCB") (part "2N7002"))
    )
    (comp (ref "Q6_3")
      (value "2N7002")
      (footprint "TO-236AB")
      (description "Q - TRANSISTOR - MOSFET (N) - 60V - 200mW")
      (fields (field (name "LCSC PART #") "C8545"))
      (libsource (lib "JLC_PCB") (part "2N7002"))
    )
    (comp (ref "Q6_4")
      (value "2N7002")
      (footprint "TO-236AB")
      (description "Q - TRANSISTOR - MOSFET (N) - 60V - 200mW")
      (fields (field (name "LCSC PART #") "C8545"))
      (libsource (lib "JLC_PCB") (part "2N7002"))
    )
    (comp (ref "Q7_1")
      (value "2N7002")
      (footprint "TO-236AB")
      (description "Q - TRANSISTOR - MOSFET (N) - 60V - 200mW")
      (fields (field (name "LCSC PART #") "C8545"))
      (libsource (lib "JLC_PCB") (part "2N7002"))
    )
    (comp (ref "Q7_2")
      (value "2N7002")
      (footprint "TO-236AB")
      (description "Q - TRANSISTOR - MOSFET (N) - 60V - 200mW")
      (fields (field (name "LCSC PART #") "C8545"))
      (libsource (lib "JLC_PCB") (part "2N7002"))
    )
    (comp (ref "Q7_3")
      (value "2N7002")
      (footprint "TO-236AB")
      (description "Q - TRANSISTOR - MOSFET (N) - 60V - 200mW")
      (fields (field (name "LCSC PART #") "C8545"))
      (libsource (lib "JLC_PCB") (part "2N7002"))
    )
    (comp (ref "Q7_4")
      (value "2N7002")
      (footprint "TO-236AB")
      (description "Q - TRANSISTOR - MOSFET (N) - 60V - 200mW")
      (fields (field (name "LCSC PART #") "C8545"))
      (libsource (lib "JLC_PCB") (part "2N7002"))
    )
    (comp (ref "Q8_1")
      (value "2N7002")
      (footprint "TO-236AB")
      (description "Q - TRANSISTOR - MOSFET (N) - 60V - 200mW")
      (fields (field (name "LCSC PART #") "C8545"))
      (libsource (lib "JLC_PCB") (part "2N7002"))
    )
    (comp (ref "Q8_2")
      (value "2N7002")
      (footprint "TO-236AB")
      (description "Q - TRANSISTOR - MOSFET (N) - 60V - 200mW")
      (fields (field (name "LCSC PART #") "C8545"))
      (libsource (lib "JLC_PCB") (part "2N7002"))
    )
    (comp (ref "Q8_3")
      (value "2N7002")
      (footprint "TO-236AB")
      (description "Q - TRANSISTOR - MOSFET (N) - 60V - 200mW")
      (fields (field (name "LCSC PART #") "C8545"))
      (libsource (lib "JLC_PCB") (part "2N7002"))
    )
    (comp (ref "Q8_4")
      (value "2N7002")
      (footprint "TO-236AB")
      (description "Q - TRANSISTOR - MOSFET (N) - 60V - 200mW")
      (fields (field (name "LCSC PART #") "C8545"))
      (libsource (lib "JLC_PCB") (part "2N7002"))
    )
    (comp (ref "Q9_1")
      (value "2N7002")
      (footprint "TO-236AB")
      (description "Q - TRANSISTOR - MOSFET (N) - 60V - 200mW")
      (fields (field (name "LCSC PART #") "C8545"))
      (libsource (lib "JLC_PCB") (part "2N7002"))
    )
    (comp (ref "Q9_2")
      (value "2N7002")
      (footprint "TO-236AB")
      (description "Q - TRANSISTOR - MOSFET (N) - 60V - 200mW")
      (fields (field (name "LCSC PART #") "C8545"))
      (libsource (lib "JLC_PCB") (part "2N7002"))
    )
    (comp (ref "Q9_3")
      (value "2N7002")
      (footprint "TO-236AB")
      (description "Q - TRANSISTOR - MOSFET (N) - 60V - 200mW")
      (fields (field (name "LCSC PART #") "C8545"))
      (libsource (lib "JLC_PCB") (part "2N7002"))
    )
    (comp (ref "Q9_4")
      (value "2N7002")
      (footprint "TO-236AB")
      (description "Q - TRANSISTOR - MOSFET (N) - 60V - 200mW")
      (fields (field (name "LCSC PART #") "C8545"))
      (libsource (lib "JLC_PCB") (part "2N7002"))
    )
  )
  (nets
    (net (code "1") (name "/G1") (class "Default")
      (node (ref "Q0_1") (pin "1") (pinfunction "G_1") (pintype "passive"))
      (node (ref "Q0_2") (pin "1") (pinfunction "G_1") (pintype "passive"))
      (node (ref "Q0_3") (pin "1") (pinfunction "G_1") (pintype "passive"))
      (node (ref "Q1_1") (pin "1") (pinfunction "G_1") (pintype "passive"))
      (node (ref "Q1_2") (pin "1") (pinfunction "G_1") (pintype "passive"))
      (node (ref "Q1_3") (pin "1") (pinfunction "G_1") (pintype "passive"))
      (node (ref "Q2_1") (pin "1") (pinfunction "G_1") (pintype "passive"))
      (node (ref "Q2_2") (pin "1") (pinfunction "G_1") (pintype "passive"))
      (node (ref "Q2_3") (pin "1") (pinfunction "G_1") (pintype "passive"))
      (node (ref "Q3_1") (pin "1") (pinfunction "G_1") (pintype "passive"))
      (node (ref "Q3_2") (pin "1") (pinfunction "G_1") (pintype "passive"))
      (node (ref "Q3_3") (pin "1") (pinfunction "G_1") (pintype "passive"))
      (node (ref "Q4_1") (pin "1") (pinfunction "G_1") (pintype "passive"))
      (node (ref "Q4_2") (pin "1") (pinfunction "G_1") (pintype "passive"))
      (node (ref "Q4_3") (pin "1") (pinfunction "G_1") (pintype "passive"))
      (node (ref "Q5_1") (pin "1") (pinfunction "G_1") (pintype "passive"))
      (node (ref "Q5_2") (pin "1") (pinfunction "G_1") (pintype "passive"))
      (node (ref "Q5_3") (pin "1") (pinfunction "G_1") (pintype "passive"))
      (node (ref "Q6_1") (pin "1") (pinfunction "G_1") (pintype "passive"))
      (node (ref "Q6_2") (pin "1") (pinfunction "G_1") (pintype "passive"))
      (node (ref "Q6_3") (pin "1") (pinfunction "G_1") (pintype "passive"))
      (node (ref "Q7_1") (pin "1") (pinfunction "G_1") (pintype "passive"))
      (node (ref "Q7_2") (pin "1") (pinfunction "G_1") (pintype "passive"))
      (node (ref "Q7_3") (pin "1") (pinfunction "G_1") (pintype "passive"))
      (node (ref "Q8_1") (pin "1") (pinfunction "G_1") (pintype "passive"))
      (node (ref "Q8_2") (pin "1") (pinfunction "G_1") (pintype "passive"))
      (node (ref "Q8_3") (pin "1") (pinfunction "G_1") (pintype "passive"))
      (node (ref "Q9_1") (pin "1") (pinfunction "G_1") (pintype "passive"))
      (node (ref "Q9_2") (pin "1") (pinfunction "G_1") (pintype "passive"))
      (node (ref "Q9_3") (pin "1") (pinfunction "G_1") (pintype "passive"))
    )
    (net (code "2") (name "/G2") (class "Default")
      (node (ref "Q0_4") (pin "1") (pinfunction "G_1") (pintype "passive"))
      (node (ref "Q1_4") (pin "1") (pinfunction "G_1") (pintype "passive"))
      (node (ref "Q2_4") (pin "1") (pinfunction "G_1") (pintype "passive"))
      (node (ref "Q3_4") (pin "1") (pinfunction "G_1") (pintype "passive"))
      (node (ref "Q4_4") (pin "1") (pinfunction "G_1") (pintype "passive"))
      (node (ref "Q5_4") (pin "1") (pinfunction "G_1") (pintype "passive"))
      (node (ref "Q6_4") (pin "1") (pinfunction "G_1") (pintype "passive"))
      (node (ref "Q7_4") (pin "1") (pinfunction "G_1") (pintype "passive"))
      (node (ref "Q8_4") (pin "1") (pinfunction "G_1") (pintype "passive"))
      (node (ref "Q9_4") (pin "1") (pinfunction "G_1") (pintype "passive"))
    )
    (net (code "3") (name "/GND") (class "Default")
      (node (ref "Q0_3") (pin "2") (pinfunction "S_2") (pintype "passive"))
      (node (ref "Q1_3") (pin "2") (pinfunction "S_2") (pintype "passive"))
      (node (ref "Q2_3") (pin "2") (pinfunction "S_2") (pintype "passive"))
      (node (ref "Q3_3") (pin "2") (pinfunction "S_2") (pintype "passive"))
      (node (ref "Q4_3") (pin "2") (pinfunction "S_2") (pintype "passive"))
      (node (ref "Q5_3") (pin "2") (pinfunction "S_2") (pintype "passive"))
      (node (ref "Q6_3") (pin "2") (pinfunction "S_2") (pintype "passive"))
      (node (ref "Q7_3") (pin "2") (pinfunction "S_2") (pintype "passive"))
      (node (ref "Q8_3") (pin "2") (pinfunction "S_2") (pintype "passive"))
      (node (ref "Q9_3") (pin "2") (pinfunction "S_2") (pintype "passive"))
    )
    (net (code "4") (name "/VCC_0") (class "Default")
      (node (ref "Q0_1") (pin "2") (pinfunction "S_2") (pintype "passive"))
      (node (ref "Q0_4") (pin "3") (pinfunction "D_3") (pintype "passive"))
      (node (ref "Q1_1") (pin "2") (pinfunction "S_2") (pintype "passive"))
      (node (ref "Q2_1") (pin "2") (pinfunction "S_2") (pintype "passive"))
      (node (ref "Q3_1") (pin "2") (pinfunction "S_2") (pintype "passive"))
      (node (ref "Q4_1") (pin "2") (pinfunction "S_2") (pintype "passive"))
      (node (ref "Q5_1") (pin "2") (pinfunction "S_2") (pintype "passive"))
      (node (ref "Q6_1") (pin "2") (pinfunction "S_2") (pintype "passive"))
      (node (ref "Q7_1") (pin "2") (pinfunction "S_2") (pintype "passive"))
      (node (ref "Q8_1") (pin "2") (pinfunction "S_2") (pintype "passive"))
      (node (ref "Q9_1") (pin "2") (pinfunction "S_2") (pintype "passive"))
    )
    (net (code "5") (name "/VCC_1") (class "Default")
      (node (ref "C0_1") (pin "1") (pinfunction "1_1") (pintype "passive"))
      (node (ref "C0_10") (pin "1") (pinfunction "1_1") (pintype "passive"))
      (node (ref "C0_2") (pin "1") (pinfunction "1_1") (pintype "passive"))
      (node (ref "C0_3") (pin "1") (pinfunction "1_1") (pintype "passive"))
      (node (ref "C0_4") (pin "1") (pinfunction "1_1") (pintype "passive"))
      (node (ref "C0_5") (pin "1") (pinfunction "1_1") (pintype "passive"))
      (node (ref "C0_6") (pin "1") (pinfunction "1_1") (pintype "passive"))
      (node (ref "C0_7") (pin "1") (pinfunction "1_1") (pintype "passive"))
      (node (ref "C0_8") (pin "1") (pinfunction "1_1") (pintype "passive"))
      (node (ref "C0_9") (pin "1") (pinfunction "1_1") (pintype "passive"))
      (node (ref "Q0_3") (pin "3") (pinfunction "D_3") (pintype "passive"))
      (node (ref "Q0_4") (pin "2") (pinfunction "S_2") (pintype "passive"))
      (node (ref "Q1_4") (pin "3") (pinfunction "D_3") (pintype "passive"))
    )
    (net (code "6") (name "/VCC_2") (class "Default")
      (node (ref "C1_1") (pin "1") (pinfunction "1_1") (pintype "passive"))
      (node (ref "C1_10") (pin "1") (pinfunction "1_1") (pintype "passive"))
      (node (ref "C1_2") (pin "1") (pinfunction "1_1") (pintype "passive"))
      (node (ref "C1_3") (pin "1") (pinfunction "1_1") (pintype "passive"))
      (node (ref "C1_4") (pin "1") (pinfunction "1_1") (pintype "passive"))
      (node (ref "C1_5") (pin "1") (pinfunction "1_1") (pintype "passive"))
      (node (ref "C1_6") (pin "1") (pinfunction "1_1") (pintype "passive"))
      (node (ref "C1_7") (pin "1") (pinfunction "1_1") (pintype "passive"))
      (node (ref "C1_8") (pin "1") (pinfunction "1_1") (pintype "passive"))
      (node (ref "C1_9") (pin "1") (pinfunction "1_1") (pintype "passive"))
      (node (ref "Q1_3") (pin "3") (pinfunction "D_3") (pintype "passive"))
      (node (ref "Q1_4") (pin "2") (pinfunction "S_2") (pintype "passive"))
      (node (ref "Q2_4") (pin "3") (pinfunction "D_3") (pintype "passive"))
    )
    (net (code "7") (name "/VCC_3") (class "Default")
      (node (ref "C2_1") (pin "1") (pinfunction "1_1") (pintype "passive"))
      (node (ref "C2_10") (pin "1") (pinfunction "1_1") (pintype "passive"))
      (node (ref "C2_2") (pin "1") (pinfunction "1_1") (pintype "passive"))
      (node (ref "C2_3") (pin "1") (pinfunction "1_1") (pintype "passive"))
      (node (ref "C2_4") (pin "1") (pinfunction "1_1") (pintype "passive"))
      (node (ref "C2_5") (pin "1") (pinfunction "1_1") (pintype "passive"))
      (node (ref "C2_6") (pin "1") (pinfunction "1_1") (pintype "passive"))
      (node (ref "C2_7") (pin "1") (pinfunction "1_1") (pintype "passive"))
      (node (ref "C2_8") (pin "1") (pinfunction "1_1") (pintype "passive"))
      (node (ref "C2_9") (pin "1") (pinfunction "1_1") (pintype "passive"))
      (node (ref "Q2_3") (pin "3") (pinfunction "D_3") (pintype "passive"))
      (node (ref "Q2_4") (pin "2") (pinfunction "S_2") (pintype "passive"))
      (node (ref "Q3_4") (pin "3") (pinfunction "D_3") (pintype "passive"))
    )
    (net (code "8") (name "/VCC_4") (class "Default")
      (node (ref "C3_1") (pin "1") (pinfunction "1_1") (pintype "passive"))
      (node (ref "C3_10") (pin "1") (pinfunction "1_1") (pintype "passive"))
      (node (ref "C3_2") (pin "1") (pinfunction "1_1") (pintype "passive"))
      (node (ref "C3_3") (pin "1") (pinfunction "1_1") (pintype "passive"))
      (node (ref "C3_4") (pin "1") (pinfunction "1_1") (pintype "passive"))
      (node (ref "C3_5") (pin "1") (pinfunction "1_1") (pintype "passive"))
      (node (ref "C3_6") (pin "1") (pinfunction "1_1") (pintype "passive"))
      (node (ref "C3_7") (pin "1") (pinfunction "1_1") (pintype "passive"))
      (node (ref "C3_8") (pin "1") (pinfunction "1_1") (pintype "passive"))
      (node (ref "C3_9") (pin "1") (pinfunction "1_1") (pintype "passive"))
      (node (ref "Q3_3") (pin "3") (pinfunction "D_3") (pintype "passive"))
      (node (ref "Q3_4") (pin "2") (pinfunction "S_2") (pintype "passive"))
      (node (ref "Q4_4") (pin "3") (pinfunction "D_3") (pintype "passive"))
    )
    (net (code "9") (name "/VCC_5") (class "Default")
      (node (ref "C4_1") (pin "1") (pinfunction "1_1") (pintype "passive"))
      (node (ref "C4_10") (pin "1") (pinfunction "1_1") (pintype "passive"))
      (node (ref "C4_2") (pin "1") (pinfunction "1_1") (pintype "passive"))
      (node (ref "C4_3") (pin "1") (pinfunction "1_1") (pintype "passive"))
      (node (ref "C4_4") (pin "1") (pinfunction "1_1") (pintype "passive"))
      (node (ref "C4_5") (pin "1") (pinfunction "1_1") (pintype "passive"))
      (node (ref "C4_6") (pin "1") (pinfunction "1_1") (pintype "passive"))
      (node (ref "C4_7") (pin "1") (pinfunction "1_1") (pintype "passive"))
      (node (ref "C4_8") (pin "1") (pinfunction "1_1") (pintype "passive"))
      (node (ref "C4_9") (pin "1") (pinfunction "1_1") (pintype "passive"))
      (node (ref "Q4_3") (pin "3") (pinfunction "D_3") (pintype "passive"))
      (node (ref "Q4_4") (pin "2") (pinfunction "S_2") (pintype "passive"))
      (node (ref "Q5_4") (pin "3") (pinfunction "D_3") (pintype "passive"))
    )
    (net (code "10") (name "/VCC_6") (class "Default")
      (node (ref "C5_1") (pin "1") (pinfunction "1_1") (pintype "passive"))
      (node (ref "C5_10") (pin "1") (pinfunction "1_1") (pintype "passive"))
      (node (ref "C5_2") (pin "1") (pinfunction "1_1") (pintype "passive"))
      (node (ref "C5_3") (pin "1") (pinfunction "1_1") (pintype "passive"))
      (node (ref "C5_4") (pin "1") (pinfunction "1_1") (pintype "passive"))
      (node (ref "C5_5") (pin "1") (pinfunction "1_1") (pintype "passive"))
      (node (ref "C5_6") (pin "1") (pinfunction "1_1") (pintype "passive"))
      (node (ref "C5_7") (pin "1") (pinfunction "1_1") (pintype "passive"))
      (node (ref "C5_8") (pin "1") (pinfunction "1_1") (pintype "passive"))
      (node (ref "C5_9") (pin "1") (pinfunction "1_1") (pintype "passive"))
      (node (ref "Q5_3") (pin "3") (pinfunction "D_3") (pintype "passive"))
      (node (ref "Q5_4") (pin "2") (pinfunction "S_2") (pintype "passive"))
      (node (ref "Q6_4") (pin "3") (pinfunction "D_3") (pintype "passive"))
    )
    (net (code "11") (name "/VCC_7") (class "Default")
      (node (ref "C6_1") (pin "1") (pinfunction "1_1") (pintype "passive"))
      (node (ref "C6_10") (pin "1") (pinfunction "1_1") (pintype "passive"))
      (node (ref "C6_2") (pin "1") (pinfunction "1_1") (pintype "passive"))
      (node (ref "C6_3") (pin "1") (pinfunction "1_1") (pintype "passive"))
      (node (ref "C6_4") (pin "1") (pinfunction "1_1") (pintype "passive"))
      (node (ref "C6_5") (pin "1") (pinfunction "1_1") (pintype "passive"))
      (node (ref "C6_6") (pin "1") (pinfunction "1_1") (pintype "passive"))
      (node (ref "C6_7") (pin "1") (pinfunction "1_1") (pintype "passive"))
      (node (ref "C6_8") (pin "1") (pinfunction "1_1") (pintype "passive"))
      (node (ref "C6_9") (pin "1") (pinfunction "1_1") (pintype "passive"))
      (node (ref "Q6_3") (pin "3") (pinfunction "D_3") (pintype "passive"))
      (node (ref "Q6_4") (pin "2") (pinfunction "S_2") (pintype "passive"))
      (node (ref "Q7_4") (pin "3") (pinfunction "D_3") (pintype "passive"))
    )
    (net (code "12") (name "/VCC_8") (class "Default")
      (node (ref "C7_1") (pin "1") (pinfunction "1_1") (pintype "passive"))
      (node (ref "C7_10") (pin "1") (pinfunction "1_1") (pintype "passive"))
      (node (ref "C7_2") (pin "1") (pinfunction "1_1") (pintype "passive"))
      (node (ref "C7_3") (pin "1") (pinfunction "1_1") (pintype "passive"))
      (node (ref "C7_4") (pin "1") (pinfunction "1_1") (pintype "passive"))
      (node (ref "C7_5") (pin "1") (pinfunction "1_1") (pintype "passive"))
      (node (ref "C7_6") (pin "1") (pinfunction "1_1") (pintype "passive"))
      (node (ref "C7_7") (pin "1") (pinfunction "1_1") (pintype "passive"))
      (node (ref "C7_8") (pin "1") (pinfunction "1_1") (pintype "passive"))
      (node (ref "C7_9") (pin "1") (pinfunction "1_1") (pintype "passive"))
      (node (ref "Q7_3") (pin "3") (pinfunction "D_3") (pintype "passive"))
      (node (ref "Q7_4") (pin "2") (pinfunction "S_2") (pintype "passive"))
      (node (ref "Q8_4") (pin "3") (pinfunction "D_3") (pintype "passive"))
    )
    (net (code "13") (name "/VCC_9") (class "Default")
      (node (ref "C8_1") (pin "1") (pinfunction "1_1") (pintype "passive"))
      (node (ref "C8_10") (pin "1") (pinfunction "1_1") (pintype "passive"))
      (node (ref "C8_2") (pin "1") (pinfunction "1_1") (pintype "passive"))
      (node (ref "C8_3") (pin "1") (pinfunction "1_1") (pintype "passive"))
      (node (ref "C8_4") (pin "1") (pinfunction "1_1") (pintype "passive"))
      (node (ref "C8_5") (pin "1") (pinfunction "1_1") (pintype "passive"))
      (node (ref "C8_6") (pin "1") (pinfunction "1_1") (pintype "passive"))
      (node (ref "C8_7") (pin "1") (pinfunction "1_1") (pintype "passive"))
      (node (ref "C8_8") (pin "1") (pinfunction "1_1") (pintype "passive"))
      (node (ref "C8_9") (pin "1") (pinfunction "1_1") (pintype "passive"))
      (node (ref "Q8_3") (pin "3") (pinfunction "D_3") (pintype "passive"))
      (node (ref "Q8_4") (pin "2") (pinfunction "S_2") (pintype "passive"))
      (node (ref "Q9_4") (pin "3") (pinfunction "D_3") (pintype "passive"))
    )
    (net (code "14") (name "/VCC_10") (class "Default")
      (node (ref "C9_1") (pin "1") (pinfunction "1_1") (pintype "passive"))
      (node (ref "C9_10") (pin "1") (pinfunction "1_1") (pintype "passive"))
      (node (ref "C9_2") (pin "1") (pinfunction "1_1") (pintype "passive"))
      (node (ref "C9_3") (pin "1") (pinfunction "1_1") (pintype "passive"))
      (node (ref "C9_4") (pin "1") (pinfunction "1_1") (pintype "passive"))
      (node (ref "C9_5") (pin "1") (pinfunction "1_1") (pintype "passive"))
      (node (ref "C9_6") (pin "1") (pinfunction "1_1") (pintype "passive"))
      (node (ref "C9_7") (pin "1") (pinfunction "1_1") (pintype "passive"))
      (node (ref "C9_8") (pin "1") (pinfunction "1_1") (pintype "passive"))
      (node (ref "C9_9") (pin "1") (pinfunction "1_1") (pintype "passive"))
      (node (ref "Q9_3") (pin "3") (pinfunction "D_3") (pintype "passive"))
      (node (ref "Q9_4") (pin "2") (pinfunction "S_2") (pintype "passive"))
    )
    (net (code "15") (name "Net-(Q0_1-D)") (class "Default")
      (node (ref "Q0_1") (pin "3") (pinfunction "D_3") (pintype "passive"))
      (node (ref "Q0_2") (pin "3") (pinfunction "D_3") (pintype "passive"))
    )
    (net (code "16") (name "Net-(Q0_2-S)") (class "Default")
      (node (ref "C0_1") (pin "2") (pinfunction "2_2") (pintype "passive"))
      (node (ref "C0_10") (pin "2") (pinfunction "2_2") (pintype "passive"))
      (node (ref "C0_2") (pin "2") (pinfunction "2_2") (pintype "passive"))
      (node (ref "C0_3") (pin "2") (pinfunction "2_2") (pintype "passive"))
      (node (ref "C0_4") (pin "2") (pinfunction "2_2") (pintype "passive"))
      (node (ref "C0_5") (pin "2") (pinfunction "2_2") (pintype "passive"))
      (node (ref "C0_6") (pin "2") (pinfunction "2_2") (pintype "passive"))
      (node (ref "C0_7") (pin "2") (pinfunction "2_2") (pintype "passive"))
      (node (ref "C0_8") (pin "2") (pinfunction "2_2") (pintype "passive"))
      (node (ref "C0_9") (pin "2") (pinfunction "2_2") (pintype "passive"))
      (node (ref "Q0_2") (pin "2") (pinfunction "S_2") (pintype "passive"))
    )
    (net (code "17") (name "Net-(Q1_1-D)") (class "Default")
      (node (ref "Q1_1") (pin "3") (pinfunction "D_3") (pintype "passive"))
      (node (ref "Q1_2") (pin "3") (pinfunction "D_3") (pintype "passive"))
    )
    (net (code "18") (name "Net-(Q1_2-S)") (class "Default")
      (node (ref "C1_1") (pin "2") (pinfunction "2_2") (pintype "passive"))
      (node (ref "C1_10") (pin "2") (pinfunction "2_2") (pintype "passive"))
      (node (ref "C1_2") (pin "2") (pinfunction "2_2") (pintype "passive"))
      (node (ref "C1_3") (pin "2") (pinfunction "2_2") (pintype "passive"))
      (node (ref "C1_4") (pin "2") (pinfunction "2_2") (pintype "passive"))
      (node (ref "C1_5") (pin "2") (pinfunction "2_2") (pintype "passive"))
      (node (ref "C1_6") (pin "2") (pinfunction "2_2") (pintype "passive"))
      (node (ref "C1_7") (pin "2") (pinfunction "2_2") (pintype "passive"))
      (node (ref "C1_8") (pin "2") (pinfunction "2_2") (pintype "passive"))
      (node (ref "C1_9") (pin "2") (pinfunction "2_2") (pintype "passive"))
      (node (ref "Q1_2") (pin "2") (pinfunction "S_2") (pintype "passive"))
    )
    (net (code "19") (name "Net-(Q2_1-D)") (class "Default")
      (node (ref "Q2_1") (pin "3") (pinfunction "D_3") (pintype "passive"))
      (node (ref "Q2_2") (pin "3") (pinfunction "D_3") (pintype "passive"))
    )
    (net (code "20") (name "Net-(Q2_2-S)") (class "Default")
      (node (ref "C2_1") (pin "2") (pinfunction "2_2") (pintype "passive"))
      (node (ref "C2_10") (pin "2") (pinfunction "2_2") (pintype "passive"))
      (node (ref "C2_2") (pin "2") (pinfunction "2_2") (pintype "passive"))
      (node (ref "C2_3") (pin "2") (pinfunction "2_2") (pintype "passive"))
      (node (ref "C2_4") (pin "2") (pinfunction "2_2") (pintype "passive"))
      (node (ref "C2_5") (pin "2") (pinfunction "2_2") (pintype "passive"))
      (node (ref "C2_6") (pin "2") (pinfunction "2_2") (pintype "passive"))
      (node (ref "C2_7") (pin "2") (pinfunction "2_2") (pintype "passive"))
      (node (ref "C2_8") (pin "2") (pinfunction "2_2") (pintype "passive"))
      (node (ref "C2_9") (pin "2") (pinfunction "2_2") (pintype "passive"))
      (node (ref "Q2_2") (pin "2") (pinfunction "S_2") (pintype "passive"))
    )
    (net (code "21") (name "Net-(Q3_1-D)") (class "Default")
      (node (ref "Q3_1") (pin "3") (pinfunction "D_3") (pintype "passive"))
      (node (ref "Q3_2") (pin "3") (pinfunction "D_3") (pintype "passive"))
    )
    (net (code "22") (name "Net-(Q3_2-S)") (class "Default")
      (node (ref "C3_1") (pin "2") (pinfunction "2_2") (pintype "passive"))
      (node (ref "C3_10") (pin "2") (pinfunction "2_2") (pintype "passive"))
      (node (ref "C3_2") (pin "2") (pinfunction "2_2") (pintype "passive"))
      (node (ref "C3_3") (pin "2") (pinfunction "2_2") (pintype "passive"))
      (node (ref "C3_4") (pin "2") (pinfunction "2_2") (pintype "passive"))
      (node (ref "C3_5") (pin "2") (pinfunction "2_2") (pintype "passive"))
      (node (ref "C3_6") (pin "2") (pinfunction "2_2") (pintype "passive"))
      (node (ref "C3_7") (pin "2") (pinfunction "2_2") (pintype "passive"))
      (node (ref "C3_8") (pin "2") (pinfunction "2_2") (pintype "passive"))
      (node (ref "C3_9") (pin "2") (pinfunction "2_2") (pintype "passive"))
      (node (ref "Q3_2") (pin "2") (pinfunction "S_2") (pintype "passive"))
    )
    (net (code "23") (name "Net-(Q4_1-D)") (class "Default")
      (node (ref "Q4_1") (pin "3") (pinfunction "D_3") (pintype "passive"))
      (node (ref "Q4_2") (pin "3") (pinfunction "D_3") (pintype "passive"))
    )
    (net (code "24") (name "Net-(Q4_2-S)") (class "Default")
      (node (ref "C4_1") (pin "2") (pinfunction "2_2") (pintype "passive"))
      (node (ref "C4_10") (pin "2") (pinfunction "2_2") (pintype "passive"))
      (node (ref "C4_2") (pin "2") (pinfunction "2_2") (pintype "passive"))
      (node (ref "C4_3") (pin "2") (pinfunction "2_2") (pintype "passive"))
      (node (ref "C4_4") (pin "2") (pinfunction "2_2") (pintype "passive"))
      (node (ref "C4_5") (pin "2") (pinfunction "2_2") (pintype "passive"))
      (node (ref "C4_6") (pin "2") (pinfunction "2_2") (pintype "passive"))
      (node (ref "C4_7") (pin "2") (pinfunction "2_2") (pintype "passive"))
      (node (ref "C4_8") (pin "2") (pinfunction "2_2") (pintype "passive"))
      (node (ref "C4_9") (pin "2") (pinfunction "2_2") (pintype "passive"))
      (node (ref "Q4_2") (pin "2") (pinfunction "S_2") (pintype "passive"))
    )
    (net (code "25") (name "Net-(Q5_1-D)") (class "Default")
      (node (ref "Q5_1") (pin "3") (pinfunction "D_3") (pintype "passive"))
      (node (ref "Q5_2") (pin "3") (pinfunction "D_3") (pintype "passive"))
    )
    (net (code "26") (name "Net-(Q5_2-S)") (class "Default")
      (node (ref "C5_1") (pin "2") (pinfunction "2_2") (pintype "passive"))
      (node (ref "C5_10") (pin "2") (pinfunction "2_2") (pintype "passive"))
      (node (ref "C5_2") (pin "2") (pinfunction "2_2") (pintype "passive"))
      (node (ref "C5_3") (pin "2") (pinfunction "2_2") (pintype "passive"))
      (node (ref "C5_4") (pin "2") (pinfunction "2_2") (pintype "passive"))
      (node (ref "C5_5") (pin "2") (pinfunction "2_2") (pintype "passive"))
      (node (ref "C5_6") (pin "2") (pinfunction "2_2") (pintype "passive"))
      (node (ref "C5_7") (pin "2") (pinfunction "2_2") (pintype "passive"))
      (node (ref "C5_8") (pin "2") (pinfunction "2_2") (pintype "passive"))
      (node (ref "C5_9") (pin "2") (pinfunction "2_2") (pintype "passive"))
      (node (ref "Q5_2") (pin "2") (pinfunction "S_2") (pintype "passive"))
    )
    (net (code "27") (name "Net-(Q6_1-D)") (class "Default")
      (node (ref "Q6_1") (pin "3") (pinfunction "D_3") (pintype "passive"))
      (node (ref "Q6_2") (pin "3") (pinfunction "D_3") (pintype "passive"))
    )
    (net (code "28") (name "Net-(Q6_2-S)") (class "Default")
      (node (ref "C6_1") (pin "2") (pinfunction "2_2") (pintype "passive"))
      (node (ref "C6_10") (pin "2") (pinfunction "2_2") (pintype "passive"))
      (node (ref "C6_2") (pin "2") (pinfunction "2_2") (pintype "passive"))
      (node (ref "C6_3") (pin "2") (pinfunction "2_2") (pintype "passive"))
      (node (ref "C6_4") (pin "2") (pinfunction "2_2") (pintype "passive"))
      (node (ref "C6_5") (pin "2") (pinfunction "2_2") (pintype "passive"))
      (node (ref "C6_6") (pin "2") (pinfunction "2_2") (pintype "passive"))
      (node (ref "C6_7") (pin "2") (pinfunction "2_2") (pintype "passive"))
      (node (ref "C6_8") (pin "2") (pinfunction "2_2") (pintype "passive"))
      (node (ref "C6_9") (pin "2") (pinfunction "2_2") (pintype "passive"))
      (node (ref "Q6_2") (pin "2") (pinfunction "S_2") (pintype "passive"))
    )
    (net (code "29") (name "Net-(Q7_1-D)") (class "Default")
      (node (ref "Q7_1") (pin "3") (pinfunction "D_3") (pintype "passive"))
      (node (ref "Q7_2") (pin "3") (pinfunction "D_3") (pintype "passive"))
    )
    (net (code "30") (name "Net-(Q7_2-S)") (class "Default")
      (node (ref "C7_1") (pin "2") (pinfunction "2_2") (pintype "passive"))
      (node (ref "C7_10") (pin "2") (pinfunction "2_2") (pintype "passive"))
      (node (ref "C7_2") (pin "2") (pinfunction "2_2") (pintype "passive"))
      (node (ref "C7_3") (pin "2") (pinfunction "2_2") (pintype "passive"))
      (node (ref "C7_4") (pin "2") (pinfunction "2_2") (pintype "passive"))
      (node (ref "C7_5") (pin "2") (pinfunction "2_2") (pintype "passive"))
      (node (ref "C7_6") (pin "2") (pinfunction "2_2") (pintype "passive"))
      (node (ref "C7_7") (pin "2") (pinfunction "2_2") (pintype "passive"))
      (node (ref "C7_8") (pin "2") (pinfunction "2_2") (pintype "passive"))
      (node (ref "C7_9") (pin "2") (pinfunction "2_2") (pintype "passive"))
      (node (ref "Q7_2") (pin "2") (pinfunction "S_2") (pintype "passive"))
    )
    (net (code "31") (name "Net-(Q8_1-D)") (class "Default")
      (node (ref "Q8_1") (pin "3") (pinfunction "D_3") (pintype "passive"))
      (node (ref "Q8_2") (pin "3") (pinfunction "D_3") (pintype "passive"))
    )
    (net (code "32") (name "Net-(Q8_2-S)") (class "Default")
      (node (ref "C8_1") (pin "2") (pinfunction "2_2") (pintype "passive"))
      (node (ref "C8_10") (pin "2") (pinfunction "2_2") (pintype "passive"))
      (node (ref "C8_2") (pin "2") (pinfunction "2_2") (pintype "passive"))
      (node (ref "C8_3") (pin "2") (pinfunction "2_2") (pintype "passive"))
      (node (ref "C8_4") (pin "2") (pinfunction "2_2") (pintype "passive"))
      (node (ref "C8_5") (pin "2") (pinfunction "2_2") (pintype "passive"))
      (node (ref "C8_6") (pin "2") (pinfunction "2_2") (pintype "passive"))
      (node (ref "C8_7") (pin "2") (pinfunction "2_2") (pintype "passive"))
      (node (ref "C8_8") (pin "2") (pinfunction "2_2") (pintype "passive"))
      (node (ref "C8_9") (pin "2") (pinfunction "2_2") (pintype "passive"))
      (node (ref "Q8_2") (pin "2") (pinfunction "S_2") (pintype "passive"))
    )
    (net (code "33") (name "Net-(Q9_1-D)") (class "Default")
      (node (ref "Q9_1") (pin "3") (pinfunction "D_3") (pintype "passive"))
      (node (ref "Q9_2") (pin "3") (pinfunction "D_3") (pintype "passive"))
    )
    (net (code "34") (name "Net-(Q9_2-S)") (class "Default")
      (node (ref "C9_1") (pin "2") (pinfunction "2_2") (pintype "passive"))
      (node (ref "C9_10") (pin "2") (pinfunction "2_2") (pintype "passive"))
      (node (ref "C9_2") (pin "2") (pinfunction "2_2") (pintype "passive"))
      (node (ref "C9_3") (pin "2") (pinfunction "2_2") (pintype "passive"))
      (node (ref "C9_4") (pin "2") (pinfunction "2_2") (pintype "passive"))
      (node (ref "C9_5") (pin "2") (pinfunction "2_2") (pintype "passive"))
      (node (ref "C9_6") (pin "2") (pinfunction "2_2") (pintype "passive"))
      (node (ref "C9_7") (pin "2") (pinfunction "2_2") (pintype "passive"))
      (node (ref "C9_8") (pin "2") (pinfunction "2_2") (pintype "passive"))
      (node (ref "C9_9") (pin "2") (pinfunction "2_2") (pintype "passive"))
      (node (ref "Q9_2") (pin "2") (pinfunction "S_2") (pintype "passive"))
    )
  )
)
